# D_cmp.net
KiCad netlist of a schematic drawn in EAGLE
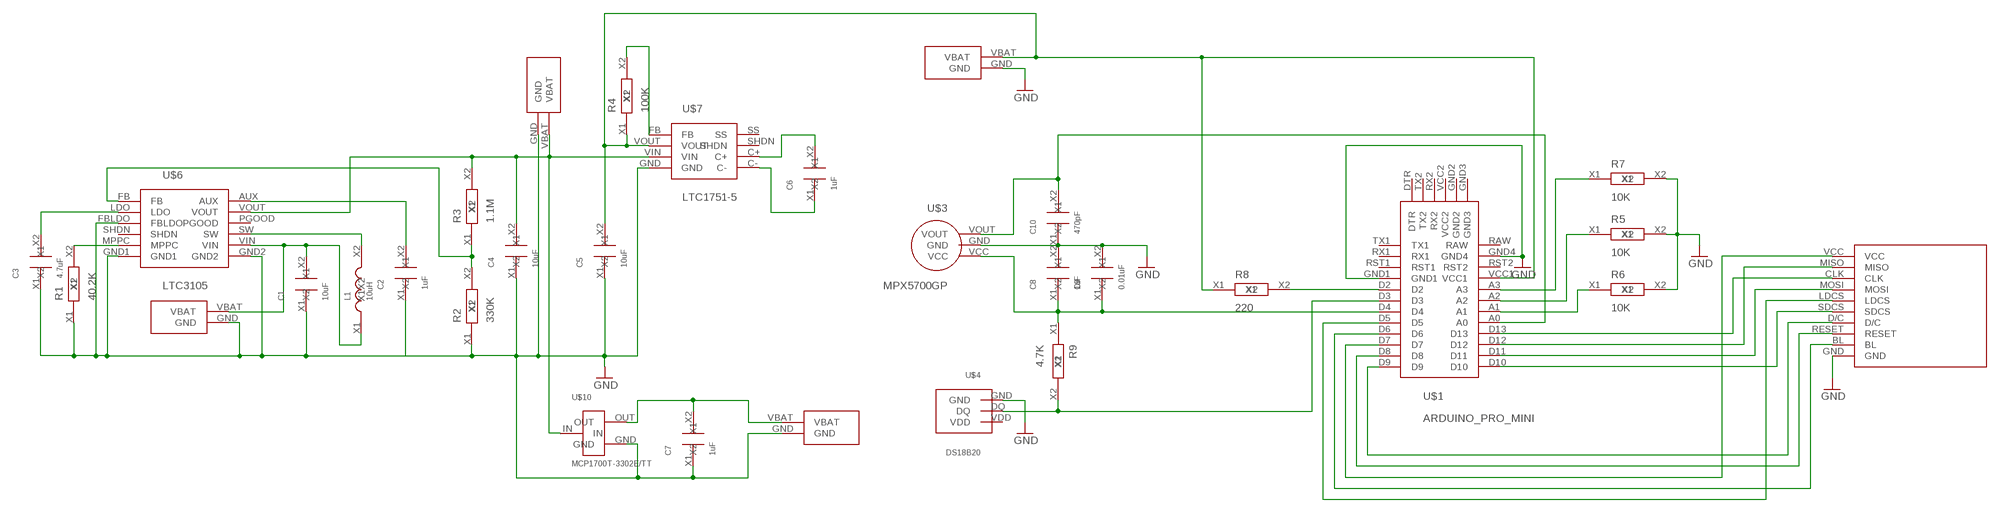
[diagram p0: schematic, sheet 1]

(export (version "E")
  (design (tool "Eeschema 10.0.6"))
  (components
    (comp (ref "C1")
      (value "10uF")
      (footprint "eagle-import:SMD_2.1X1.25")
      (libsource (lib "eagle-import") (part "C_SMD_2.1X1.25"))
    )
    (comp (ref "C2")
      (value "1uF")
      (footprint "eagle-import:SMD_2.1X1.25")
      (libsource (lib "eagle-import") (part "C_SMD_2.1X1.25"))
    )
    (comp (ref "C3")
      (value "4.7uF")
      (footprint "eagle-import:SMD_2.1X1.25")
      (libsource (lib "eagle-import") (part "C_SMD_2.1X1.25"))
    )
    (comp (ref "C4")
      (value "10uF")
      (footprint "eagle-import:SMD_2.1X1.25")
      (libsource (lib "eagle-import") (part "C_SMD_2.1X1.25"))
    )
    (comp (ref "C5")
      (value "10uF")
      (footprint "eagle-import:SMD_2.1X1.25")
      (libsource (lib "eagle-import") (part "C_SMD_2.1X1.25"))
    )
    (comp (ref "C6")
      (value "1uF")
      (footprint "eagle-import:SMD_2.1X1.25")
      (libsource (lib "eagle-import") (part "C_SMD_2.1X1.25"))
    )
    (comp (ref "C7")
      (value "1uF")
      (footprint "eagle-import:SMD_2.1X1.25")
      (libsource (lib "eagle-import") (part "C_SMD_2.1X1.25"))
    )
    (comp (ref "C8")
      (value "1uF")
      (footprint "eagle-import:SMD_2.1X1.25")
      (libsource (lib "eagle-import") (part "C_SMD_2.1X1.25"))
    )
    (comp (ref "C9")
      (value "0.01uF")
      (footprint "eagle-import:SMD_2.1X1.25")
      (libsource (lib "eagle-import") (part "C_SMD_2.1X1.25"))
    )
    (comp (ref "C10")
      (value "470pF")
      (footprint "eagle-import:SMD_2.1X1.25")
      (libsource (lib "eagle-import") (part "C_SMD_2.1X1.25"))
    )
    (comp (ref "L1")
      (value "10uH")
      (footprint "eagle-import:SMD_2.1X1.25")
      (libsource (lib "eagle-import") (part "L_SMD_2.1X1.25"))
    )
    (comp (ref "R1")
      (value "40.2K")
      (footprint "eagle-import:SMD_2.1X1.25")
      (libsource (lib "eagle-import") (part "R_SMD_2.1X1.25"))
    )
    (comp (ref "R2")
      (value "330K")
      (footprint "eagle-import:SMD_2.1X1.25")
      (libsource (lib "eagle-import") (part "R_SMD_2.1X1.25"))
    )
    (comp (ref "R3")
      (value "1.1M")
      (footprint "eagle-import:SMD_2.1X1.25")
      (libsource (lib "eagle-import") (part "R_SMD_2.1X1.25"))
    )
    (comp (ref "R4")
      (value "100K")
      (footprint "eagle-import:SMD_2.1X1.25")
      (libsource (lib "eagle-import") (part "R_SMD_2.1X1.25"))
    )
    (comp (ref "R5")
      (value "10K")
      (footprint "eagle-import:SMD_2.1X1.25")
      (libsource (lib "eagle-import") (part "R_SMD_2.1X1.25"))
    )
    (comp (ref "R6")
      (value "10K")
      (footprint "eagle-import:SMD_2.1X1.25")
      (libsource (lib "eagle-import") (part "R_SMD_2.1X1.25"))
    )
    (comp (ref "R7")
      (value "10K")
      (footprint "eagle-import:SMD_2.1X1.25")
      (libsource (lib "eagle-import") (part "R_SMD_2.1X1.25"))
    )
    (comp (ref "R8")
      (value "220")
      (footprint "eagle-import:SMD_2.1X1.25")
      (libsource (lib "eagle-import") (part "R_SMD_2.1X1.25"))
    )
    (comp (ref "R9")
      (value "4.7K")
      (footprint "eagle-import:SMD_2.1X1.25")
      (libsource (lib "eagle-import") (part "R_SMD_2.1X1.25"))
    )
    (comp (ref "U$1")
      (value "ARDUINO_PRO_MINI")
      (footprint "eagle-import:ARDUINO_PRO_MINI")
      (libsource (lib "eagle-import") (part "ARDUINO_PRO_MINI"))
    )
    (comp (ref "U$2")
      (value "TFT_LCD")
      (footprint "eagle-import:TFT_LCD")
      (libsource (lib "eagle-import") (part "TFT_LCD"))
    )
    (comp (ref "U$3")
      (value "MPX5700GP")
      (footprint "eagle-import:MPX5700GP")
      (libsource (lib "eagle-import") (part "MPX5700GP"))
    )
    (comp (ref "U$4")
      (value "DS18B20")
      (footprint "eagle-import:DS18B20")
      (libsource (lib "eagle-import") (part "DS18B20"))
    )
    (comp (ref "U$5")
      (value "BAT_PLUG")
      (footprint "eagle-import:BAT_PLUG")
      (libsource (lib "eagle-import") (part "BAT_PLUG"))
    )
    (comp (ref "U$6")
      (value "LTC3105")
      (footprint "eagle-import:LTC3105")
      (libsource (lib "eagle-import") (part "LTC3105"))
    )
    (comp (ref "U$7")
      (value "LTC1751-5")
      (footprint "eagle-import:LTC1751-5")
      (libsource (lib "eagle-import") (part "LTC1751-5"))
    )
    (comp (ref "U$8")
      (value "BAT_PLUG")
      (footprint "eagle-import:BAT_PLUG")
      (libsource (lib "eagle-import") (part "BAT_PLUG"))
    )
    (comp (ref "U$9")
      (value "BAT_PLUG")
      (footprint "eagle-import:BAT_PLUG")
      (libsource (lib "eagle-import") (part "BAT_PLUG"))
    )
    (comp (ref "U$10")
      (value "MCP1700T-3302E/TT")
      (footprint "eagle-import:MCP1700T-3302E_TT")
      (libsource (lib "eagle-import") (part "MCP1700T-3302E/TT"))
    )
    (comp (ref "U$11")
      (value "BAT_PLUG")
      (footprint "eagle-import:BAT_PLUG")
      (libsource (lib "eagle-import") (part "BAT_PLUG"))
    )
  )
  (nets
    (net (code "1") (name "GND") (class "Default")
      (node (ref "C1") (pin "X1") (pinfunction "X1_X1") (pintype "bidirectional"))
      (node (ref "C10") (pin "X1") (pinfunction "X1_X1") (pintype "bidirectional"))
      (node (ref "C2") (pin "X1") (pinfunction "X1_X1") (pintype "bidirectional"))
      (node (ref "C3") (pin "X1") (pinfunction "X1_X1") (pintype "bidirectional"))
      (node (ref "C4") (pin "X1") (pinfunction "X1_X1") (pintype "bidirectional"))
      (node (ref "C5") (pin "X1") (pinfunction "X1_X1") (pintype "bidirectional"))
      (node (ref "C7") (pin "X1") (pinfunction "X1_X1") (pintype "bidirectional"))
      (node (ref "C8") (pin "X2") (pinfunction "X2_X2") (pintype "bidirectional"))
      (node (ref "C9") (pin "X2") (pinfunction "X2_X2") (pintype "bidirectional"))
      (node (ref "R1") (pin "X1") (pinfunction "X1_X1") (pintype "bidirectional"))
      (node (ref "R2") (pin "X1") (pinfunction "X1_X1") (pintype "bidirectional"))
      (node (ref "R5") (pin "X2") (pinfunction "X2_X2") (pintype "bidirectional"))
      (node (ref "R6") (pin "X2") (pinfunction "X2_X2") (pintype "bidirectional"))
      (node (ref "R7") (pin "X2") (pinfunction "X2_X2") (pintype "bidirectional"))
      (node (ref "U$1") (pin "GND1") (pinfunction "GND1_GND1") (pintype "bidirectional"))
      (node (ref "U$1") (pin "GND4") (pinfunction "GND4_GND4") (pintype "bidirectional"))
      (node (ref "U$10") (pin "GND") (pinfunction "GND_GND") (pintype "bidirectional"))
      (node (ref "U$11") (pin "GND") (pinfunction "GND_GND") (pintype "bidirectional"))
      (node (ref "U$2") (pin "GND") (pinfunction "GND_GND") (pintype "bidirectional"))
      (node (ref "U$3") (pin "GND") (pinfunction "GND_GND") (pintype "bidirectional"))
      (node (ref "U$4") (pin "GND") (pinfunction "GND_GND") (pintype "bidirectional"))
      (node (ref "U$5") (pin "GND") (pinfunction "GND_GND") (pintype "bidirectional"))
      (node (ref "U$6") (pin "FBLDO") (pinfunction "FBLDO_FBLDO") (pintype "bidirectional"))
      (node (ref "U$6") (pin "GND1") (pinfunction "GND1_GND1") (pintype "bidirectional"))
      (node (ref "U$6") (pin "GND2") (pinfunction "GND2_GND2") (pintype "bidirectional"))
      (node (ref "U$7") (pin "GND") (pinfunction "GND_GND") (pintype "bidirectional"))
      (node (ref "U$8") (pin "GND") (pinfunction "GND_GND") (pintype "bidirectional"))
      (node (ref "U$9") (pin "GND") (pinfunction "GND_GND") (pintype "bidirectional"))
    )
    (net (code "2") (name "Net-(C1-PadX2)") (class "Default")
      (node (ref "C1") (pin "X2") (pinfunction "X2_X2") (pintype "bidirectional"))
      (node (ref "L1") (pin "X1") (pinfunction "X1_X1") (pintype "bidirectional"))
      (node (ref "U$6") (pin "VIN") (pinfunction "VIN_VIN") (pintype "bidirectional"))
      (node (ref "U$8") (pin "VBAT") (pinfunction "VBAT_VBAT") (pintype "bidirectional"))
    )
    (net (code "3") (name "Net-(C2-PadX2)") (class "Default")
      (node (ref "C2") (pin "X2") (pinfunction "X2_X2") (pintype "bidirectional"))
      (node (ref "U$6") (pin "AUX") (pinfunction "AUX_AUX") (pintype "bidirectional"))
    )
    (net (code "4") (name "Net-(C3-PadX2)") (class "Default")
      (node (ref "C3") (pin "X2") (pinfunction "X2_X2") (pintype "bidirectional"))
      (node (ref "U$6") (pin "LDO") (pinfunction "LDO_LDO") (pintype "bidirectional"))
    )
    (net (code "5") (name "Net-(C4-PadX2)") (class "Default")
      (node (ref "C4") (pin "X2") (pinfunction "X2_X2") (pintype "bidirectional"))
      (node (ref "R3") (pin "X2") (pinfunction "X2_X2") (pintype "bidirectional"))
      (node (ref "U$10") (pin "IN") (pinfunction "IN_IN") (pintype "bidirectional"))
      (node (ref "U$6") (pin "VOUT") (pinfunction "VOUT_VOUT") (pintype "bidirectional"))
      (node (ref "U$7") (pin "VIN") (pinfunction "VIN_VIN") (pintype "bidirectional"))
      (node (ref "U$9") (pin "VBAT") (pinfunction "VBAT_VBAT") (pintype "bidirectional"))
    )
    (net (code "6") (name "Net-(C5-PadX2)") (class "Default")
      (node (ref "C5") (pin "X2") (pinfunction "X2_X2") (pintype "bidirectional"))
      (node (ref "R4") (pin "X1") (pinfunction "X1_X1") (pintype "bidirectional"))
      (node (ref "R8") (pin "X1") (pinfunction "X1_X1") (pintype "bidirectional"))
      (node (ref "U$1") (pin "VCC1") (pinfunction "VCC1_VCC1") (pintype "bidirectional"))
      (node (ref "U$5") (pin "VBAT") (pinfunction "VBAT_VBAT") (pintype "bidirectional"))
      (node (ref "U$7") (pin "VOUT") (pinfunction "VOUT_VOUT") (pintype "bidirectional"))
    )
    (net (code "7") (name "Net-(C6-PadX1)") (class "Default")
      (node (ref "C6") (pin "X1") (pinfunction "X1_X1") (pintype "bidirectional"))
      (node (ref "U$7") (pin "C-") (pinfunction "C-_C-") (pintype "bidirectional"))
    )
    (net (code "8") (name "Net-(C6-PadX2)") (class "Default")
      (node (ref "C6") (pin "X2") (pinfunction "X2_X2") (pintype "bidirectional"))
      (node (ref "U$7") (pin "C+") (pinfunction "C+_C+") (pintype "bidirectional"))
    )
    (net (code "9") (name "Net-(C7-PadX2)") (class "Default")
      (node (ref "C7") (pin "X2") (pinfunction "X2_X2") (pintype "bidirectional"))
      (node (ref "U$10") (pin "OUT") (pinfunction "OUT_OUT") (pintype "bidirectional"))
      (node (ref "U$11") (pin "VBAT") (pinfunction "VBAT_VBAT") (pintype "bidirectional"))
    )
    (net (code "10") (name "Net-(C8-PadX1)") (class "Default")
      (node (ref "C8") (pin "X1") (pinfunction "X1_X1") (pintype "bidirectional"))
      (node (ref "C9") (pin "X1") (pinfunction "X1_X1") (pintype "bidirectional"))
      (node (ref "R9") (pin "X1") (pinfunction "X1_X1") (pintype "bidirectional"))
      (node (ref "U$1") (pin "D4") (pinfunction "D4_D4") (pintype "bidirectional"))
      (node (ref "U$3") (pin "VCC") (pinfunction "VCC_VCC") (pintype "bidirectional"))
    )
    (net (code "11") (name "Net-(C10-PadX2)") (class "Default")
      (node (ref "C10") (pin "X2") (pinfunction "X2_X2") (pintype "bidirectional"))
      (node (ref "U$1") (pin "A0") (pinfunction "A0_A0") (pintype "bidirectional"))
      (node (ref "U$3") (pin "VOUT") (pinfunction "VOUT_VOUT") (pintype "bidirectional"))
    )
    (net (code "12") (name "Net-(L1-PadX2)") (class "Default")
      (node (ref "L1") (pin "X2") (pinfunction "X2_X2") (pintype "bidirectional"))
      (node (ref "U$6") (pin "SW") (pinfunction "SW_SW") (pintype "bidirectional"))
    )
    (net (code "13") (name "Net-(R1-PadX2)") (class "Default")
      (node (ref "R1") (pin "X2") (pinfunction "X2_X2") (pintype "bidirectional"))
      (node (ref "U$6") (pin "MPPC") (pinfunction "MPPC_MPPC") (pintype "bidirectional"))
    )
    (net (code "14") (name "Net-(R2-PadX2)") (class "Default")
      (node (ref "R2") (pin "X2") (pinfunction "X2_X2") (pintype "bidirectional"))
      (node (ref "R3") (pin "X1") (pinfunction "X1_X1") (pintype "bidirectional"))
      (node (ref "U$6") (pin "FB") (pinfunction "FB_FB") (pintype "bidirectional"))
    )
    (net (code "15") (name "Net-(R4-PadX2)") (class "Default")
      (node (ref "R4") (pin "X2") (pinfunction "X2_X2") (pintype "bidirectional"))
      (node (ref "U$7") (pin "FB") (pinfunction "FB_FB") (pintype "bidirectional"))
    )
    (net (code "16") (name "Net-(R5-PadX1)") (class "Default")
      (node (ref "R5") (pin "X1") (pinfunction "X1_X1") (pintype "bidirectional"))
      (node (ref "U$1") (pin "A2") (pinfunction "A2_A2") (pintype "bidirectional"))
    )
    (net (code "17") (name "Net-(R6-PadX1)") (class "Default")
      (node (ref "R6") (pin "X1") (pinfunction "X1_X1") (pintype "bidirectional"))
      (node (ref "U$1") (pin "A1") (pinfunction "A1_A1") (pintype "bidirectional"))
    )
    (net (code "18") (name "Net-(R7-PadX1)") (class "Default")
      (node (ref "R7") (pin "X1") (pinfunction "X1_X1") (pintype "bidirectional"))
      (node (ref "U$1") (pin "A3") (pinfunction "A3_A3") (pintype "bidirectional"))
    )
    (net (code "19") (name "Net-(R8-PadX2)") (class "Default")
      (node (ref "R8") (pin "X2") (pinfunction "X2_X2") (pintype "bidirectional"))
      (node (ref "U$1") (pin "D2") (pinfunction "D2_D2") (pintype "bidirectional"))
    )
    (net (code "20") (name "Net-(R9-PadX2)") (class "Default")
      (node (ref "R9") (pin "X2") (pinfunction "X2_X2") (pintype "bidirectional"))
      (node (ref "U$1") (pin "D3") (pinfunction "D3_D3") (pintype "bidirectional"))
      (node (ref "U$4") (pin "DQ") (pinfunction "DQ_DQ") (pintype "bidirectional"))
    )
    (net (code "21") (name "Net-(U$1-PadD5)") (class "Default")
      (node (ref "U$1") (pin "D5") (pinfunction "D5_D5") (pintype "bidirectional"))
      (node (ref "U$2") (pin "LDCS") (pinfunction "LDCS_LDCS") (pintype "bidirectional"))
    )
    (net (code "22") (name "Net-(U$1-PadD6)") (class "Default")
      (node (ref "U$1") (pin "D6") (pinfunction "D6_D6") (pintype "bidirectional"))
      (node (ref "U$2") (pin "BL") (pinfunction "BL_BL") (pintype "bidirectional"))
    )
    (net (code "23") (name "Net-(U$1-PadD7)") (class "Default")
      (node (ref "U$1") (pin "D7") (pinfunction "D7_D7") (pintype "bidirectional"))
      (node (ref "U$2") (pin "VCC") (pinfunction "VCC_VCC") (pintype "bidirectional"))
    )
    (net (code "24") (name "Net-(U$1-PadD8)") (class "Default")
      (node (ref "U$1") (pin "D8") (pinfunction "D8_D8") (pintype "bidirectional"))
      (node (ref "U$2") (pin "RESET") (pinfunction "RESET_RESET") (pintype "bidirectional"))
    )
    (net (code "25") (name "Net-(U$1-PadD9)") (class "Default")
      (node (ref "U$1") (pin "D9") (pinfunction "D9_D9") (pintype "bidirectional"))
      (node (ref "U$2") (pin "D/C") (pinfunction "D/C_D/C") (pintype "bidirectional"))
    )
    (net (code "26") (name "Net-(U$1-PadD10)") (class "Default")
      (node (ref "U$1") (pin "D10") (pinfunction "D10_D10") (pintype "bidirectional"))
      (node (ref "U$2") (pin "SDCS") (pinfunction "SDCS_SDCS") (pintype "bidirectional"))
    )
    (net (code "27") (name "Net-(U$1-PadD11)") (class "Default")
      (node (ref "U$1") (pin "D11") (pinfunction "D11_D11") (pintype "bidirectional"))
      (node (ref "U$2") (pin "MOSI") (pinfunction "MOSI_MOSI") (pintype "bidirectional"))
    )
    (net (code "28") (name "Net-(U$1-PadD12)") (class "Default")
      (node (ref "U$1") (pin "D12") (pinfunction "D12_D12") (pintype "bidirectional"))
      (node (ref "U$2") (pin "MISO") (pinfunction "MISO_MISO") (pintype "bidirectional"))
    )
    (net (code "29") (name "Net-(U$1-PadD13)") (class "Default")
      (node (ref "U$1") (pin "D13") (pinfunction "D13_D13") (pintype "bidirectional"))
      (node (ref "U$2") (pin "CLK") (pinfunction "CLK_CLK") (pintype "bidirectional"))
    )
    (net (code "30") (name "unconnected-(U$1-PadDTR)") (class "Default")
      (node (ref "U$1") (pin "DTR") (pinfunction "DTR_DTR") (pintype "bidirectional"))
    )
    (net (code "31") (name "unconnected-(U$1-PadGND2)") (class "Default")
      (node (ref "U$1") (pin "GND2") (pinfunction "GND2_GND2") (pintype "bidirectional"))
    )
    (net (code "32") (name "unconnected-(U$1-PadGND3)") (class "Default")
      (node (ref "U$1") (pin "GND3") (pinfunction "GND3_GND3") (pintype "bidirectional"))
    )
    (net (code "33") (name "unconnected-(U$1-PadRAW)") (class "Default")
      (node (ref "U$1") (pin "RAW") (pinfunction "RAW_RAW") (pintype "bidirectional"))
    )
    (net (code "34") (name "unconnected-(U$1-PadRST1)") (class "Default")
      (node (ref "U$1") (pin "RST1") (pinfunction "RST1_RST1") (pintype "bidirectional"))
    )
    (net (code "35") (name "unconnected-(U$1-PadRST2)") (class "Default")
      (node (ref "U$1") (pin "RST2") (pinfunction "RST2_RST2") (pintype "bidirectional"))
    )
    (net (code "36") (name "unconnected-(U$1-PadRX1)") (class "Default")
      (node (ref "U$1") (pin "RX1") (pinfunction "RX1_RX1") (pintype "bidirectional"))
    )
    (net (code "37") (name "unconnected-(U$1-PadRX2)") (class "Default")
      (node (ref "U$1") (pin "RX2") (pinfunction "RX2_RX2") (pintype "bidirectional"))
    )
    (net (code "38") (name "unconnected-(U$1-PadTX1)") (class "Default")
      (node (ref "U$1") (pin "TX1") (pinfunction "TX1_TX1") (pintype "bidirectional"))
    )
    (net (code "39") (name "unconnected-(U$1-PadTX2)") (class "Default")
      (node (ref "U$1") (pin "TX2") (pinfunction "TX2_TX2") (pintype "bidirectional"))
    )
    (net (code "40") (name "unconnected-(U$1-PadVCC2)") (class "Default")
      (node (ref "U$1") (pin "VCC2") (pinfunction "VCC2_VCC2") (pintype "bidirectional"))
    )
    (net (code "41") (name "unconnected-(U$4-PadVDD)") (class "Default")
      (node (ref "U$4") (pin "VDD") (pinfunction "VDD_VDD") (pintype "bidirectional"))
    )
    (net (code "42") (name "unconnected-(U$6-PadPGOOD)") (class "Default")
      (node (ref "U$6") (pin "PGOOD") (pinfunction "PGOOD_PGOOD") (pintype "bidirectional"))
    )
    (net (code "43") (name "unconnected-(U$6-PadSHDN)") (class "Default")
      (node (ref "U$6") (pin "SHDN") (pinfunction "SHDN_SHDN") (pintype "bidirectional"))
    )
    (net (code "44") (name "unconnected-(U$7-PadSHDN)") (class "Default")
      (node (ref "U$7") (pin "SHDN") (pinfunction "SHDN_SHDN") (pintype "bidirectional"))
    )
    (net (code "45") (name "unconnected-(U$7-PadSS)") (class "Default")
      (node (ref "U$7") (pin "SS") (pinfunction "SS_SS") (pintype "bidirectional"))
    )
  )
)
